# 2final.net
KiCad netlist of a schematic drawn in EAGLE
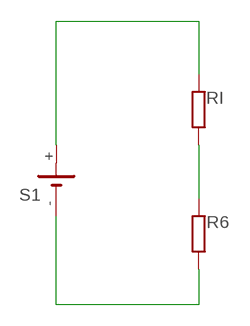
[diagram p0: schematic, sheet 1]

(export (version "E")
  (design (tool "Eeschema 10.0.6"))
  (components
    (comp (ref "R6")
      (value "570R")
      (footprint "eagle-import:0204_7")
      (libsource (lib "eagle-import") (part "R-EU_0204/7"))
    )
    (comp (ref "RI")
      (value "220R")
      (footprint "eagle-import:0204_7")
      (libsource (lib "eagle-import") (part "R-EU_0204/7"))
    )
    (comp (ref "S1")
      (value "CH291-1220LF")
      (footprint "eagle-import:CH291-1220LF")
      (libsource (lib "eagle-import") (part "CH291-1220LF"))
    )
  )
  (nets
    (net (code "1") (name "Net-(R6-Pad1)") (class "Default")
      (node (ref "R6") (pin "1") (pinfunction "1_1") (pintype "passive"))
      (node (ref "S1") (pin "-") (pinfunction "-_-") (pintype "passive"))
    )
    (net (code "2") (name "Net-(R6-Pad2)") (class "Default")
      (node (ref "R6") (pin "2") (pinfunction "2_2") (pintype "passive"))
      (node (ref "RI") (pin "1") (pinfunction "1_1") (pintype "passive"))
    )
    (net (code "3") (name "Net-(RI-Pad2)") (class "Default")
      (node (ref "RI") (pin "2") (pinfunction "2_2") (pintype "passive"))
      (node (ref "S1") (pin "+") (pinfunction "+_+") (pintype "passive"))
    )
  )
)
